# releBoard_v20.net
KiCad netlist of a schematic drawn in EAGLE
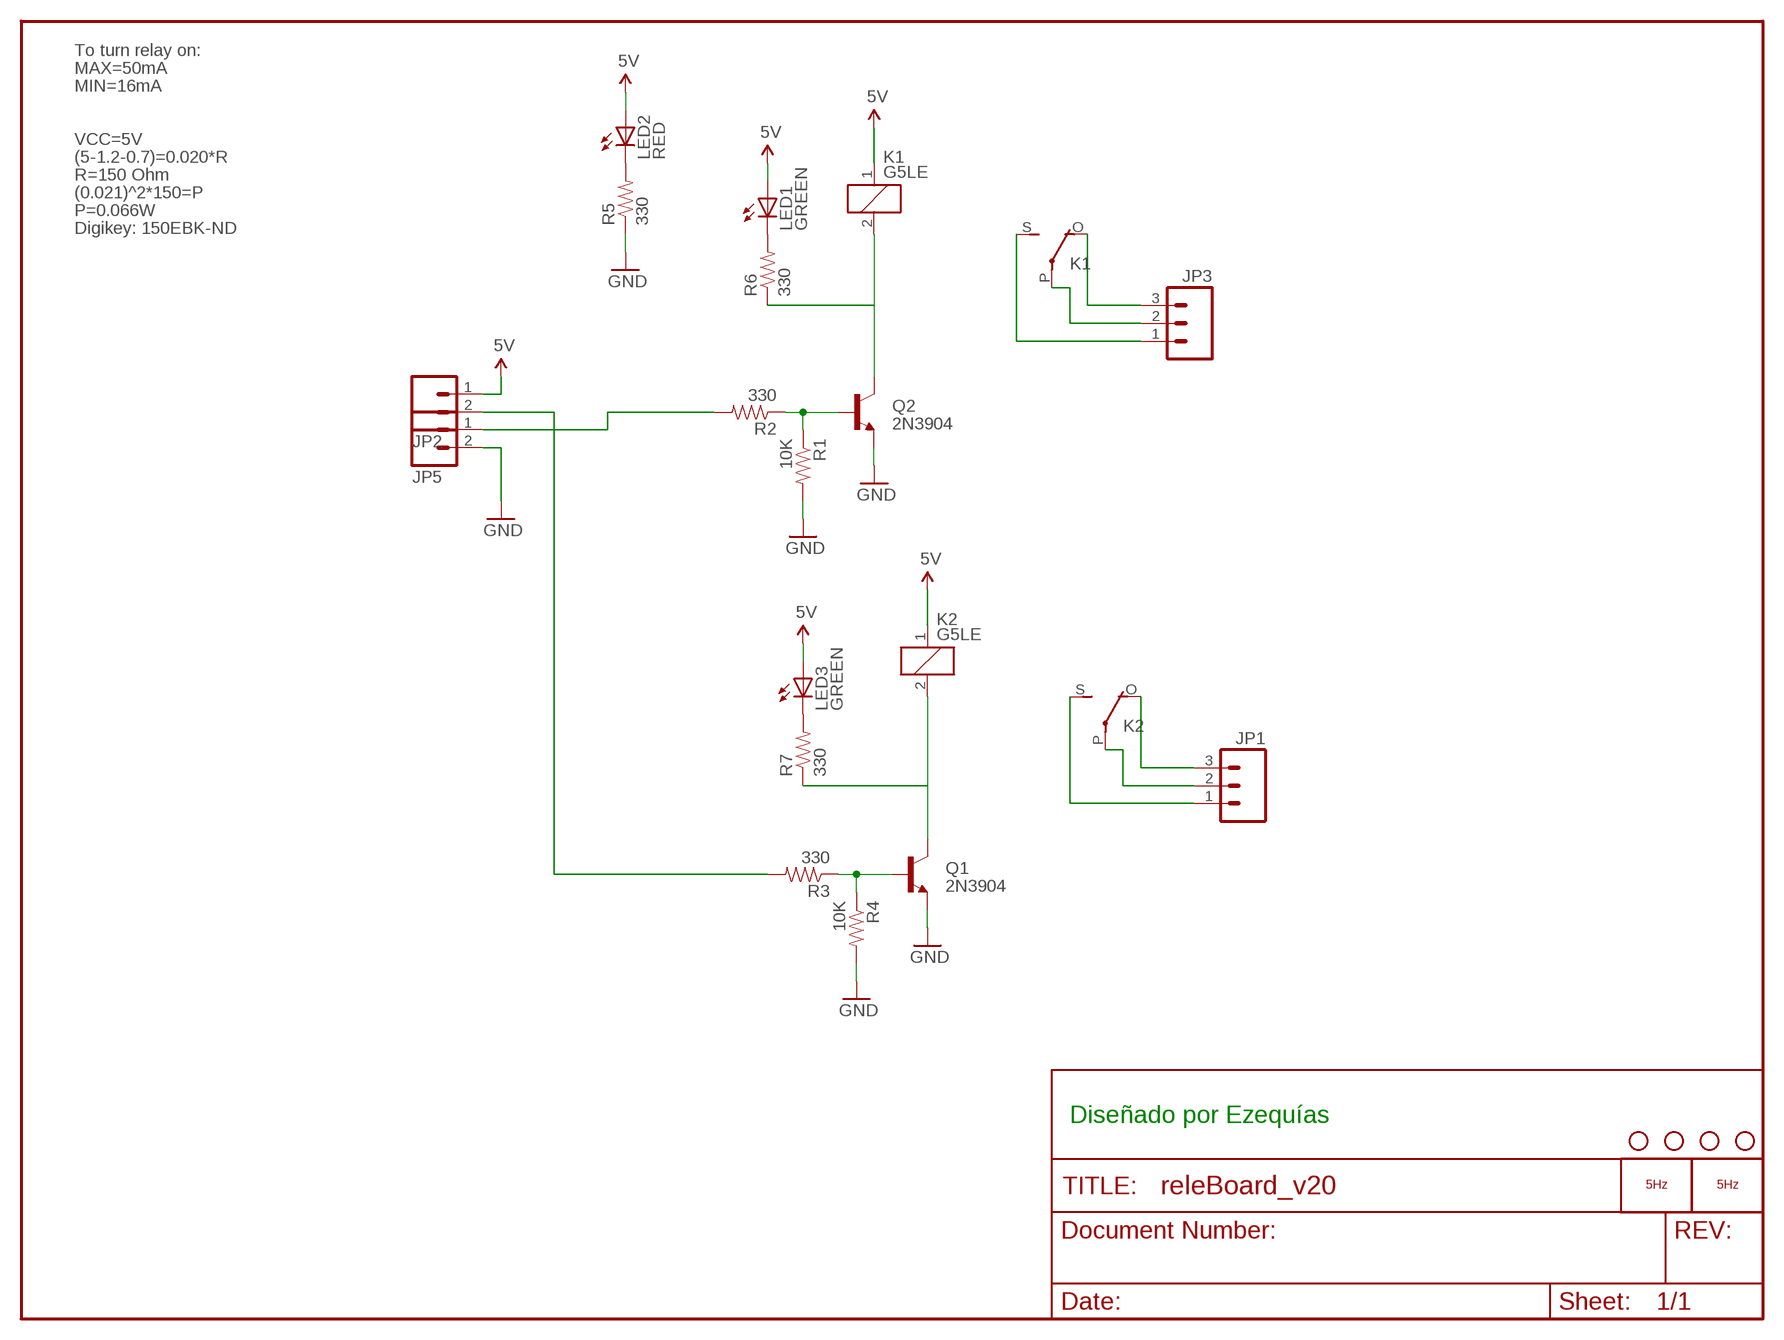
[diagram p0: schematic, sheet 1]

(export (version "E")
  (design (tool "Eeschema 10.0.6"))
  (components
    (comp (ref "JP1")
      (value "M03-SCREW-5MM")
      (footprint "eagle-import:SCREWTERMINAL-5MM-3")
      (libsource (lib "eagle-import") (part "M03-SCREW-5MM"))
    )
    (comp (ref "JP2")
      (value "M025MM")
      (footprint "eagle-import:SCREWTERMINAL-5MM-2")
      (libsource (lib "eagle-import") (part "M025MM"))
    )
    (comp (ref "JP3")
      (value "M03-SCREW-5MM")
      (footprint "eagle-import:SCREWTERMINAL-5MM-3")
      (libsource (lib "eagle-import") (part "M03-SCREW-5MM"))
    )
    (comp (ref "JP5")
      (value "M025MM")
      (footprint "eagle-import:SCREWTERMINAL-5MM-2")
      (libsource (lib "eagle-import") (part "M025MM"))
    )
    (comp (ref "K1")
      (value "G5LE")
      (footprint "eagle-import:G5LE")
      (libsource (lib "eagle-import") (part "G5LE"))
    )
    (comp (ref "K2")
      (value "G5LE")
      (footprint "eagle-import:G5LE")
      (libsource (lib "eagle-import") (part "G5LE"))
    )
    (comp (ref "LED1")
      (value "GREEN")
      (footprint "eagle-import:LED-0603")
      (libsource (lib "eagle-import") (part "LED0603"))
    )
    (comp (ref "LED2")
      (value "RED")
      (footprint "eagle-import:LED-0603")
      (libsource (lib "eagle-import") (part "LED0603"))
    )
    (comp (ref "LED3")
      (value "GREEN")
      (footprint "eagle-import:LED-0603")
      (libsource (lib "eagle-import") (part "LED0603"))
    )
    (comp (ref "LOGO1")
      (value "LOGO_5HZ_H_15MM")
      (footprint "eagle-import:5HZ_LOGO_H_15MM")
      (libsource (lib "eagle-import") (part "LOGO_5HZ_H_15MM"))
    )
    (comp (ref "LOGO2")
      (value "LOGO_5HZ_WEB_COOPER_10MM")
      (footprint "eagle-import:5HZ_WEB_COOPER_10MM")
      (libsource (lib "eagle-import") (part "LOGO_5HZ_WEB_COOPER_10MM"))
    )
    (comp (ref "Q1")
      (value "2N3904")
      (footprint "eagle-import:SOT23")
      (libsource (lib "eagle-import") (part "TRANSISTOR_NPNSOT23"))
    )
    (comp (ref "Q2")
      (value "2N3904")
      (footprint "eagle-import:SOT23")
      (libsource (lib "eagle-import") (part "TRANSISTOR_NPNSOT23"))
    )
    (comp (ref "R1")
      (value "10K")
      (footprint "eagle-import:0603-RES")
      (libsource (lib "eagle-import") (part "RESISTOR0603-RES"))
    )
    (comp (ref "R2")
      (value "330")
      (footprint "eagle-import:0603-RES")
      (libsource (lib "eagle-import") (part "RESISTOR0603-RES"))
    )
    (comp (ref "R3")
      (value "330")
      (footprint "eagle-import:0603-RES")
      (libsource (lib "eagle-import") (part "RESISTOR0603-RES"))
    )
    (comp (ref "R4")
      (value "10K")
      (footprint "eagle-import:0603-RES")
      (libsource (lib "eagle-import") (part "RESISTOR0603-RES"))
    )
    (comp (ref "R5")
      (value "330")
      (footprint "eagle-import:0603-RES")
      (libsource (lib "eagle-import") (part "RESISTOR0603-RES"))
    )
    (comp (ref "R6")
      (value "330")
      (footprint "eagle-import:0603-RES")
      (libsource (lib "eagle-import") (part "RESISTOR0603-RES"))
    )
    (comp (ref "R7")
      (value "330")
      (footprint "eagle-import:0603-RES")
      (libsource (lib "eagle-import") (part "RESISTOR0603-RES"))
    )
    (comp (ref "U$3")
      (value "STAND-OFF")
      (footprint "eagle-import:STAND-OFF")
      (libsource (lib "eagle-import") (part "STAND-OFF"))
    )
    (comp (ref "U$4")
      (value "STAND-OFF")
      (footprint "eagle-import:STAND-OFF")
      (libsource (lib "eagle-import") (part "STAND-OFF"))
    )
    (comp (ref "U$5")
      (value "STAND-OFF")
      (footprint "eagle-import:STAND-OFF")
      (libsource (lib "eagle-import") (part "STAND-OFF"))
    )
    (comp (ref "U$7")
      (value "STAND-OFF")
      (footprint "eagle-import:STAND-OFF")
      (libsource (lib "eagle-import") (part "STAND-OFF"))
    )
  )
  (nets
    (net (code "1") (name "5V") (class "Default")
      (node (ref "JP2") (pin "1") (pinfunction "1_1") (pintype "passive"))
      (node (ref "K1") (pin "1") (pinfunction "1_1") (pintype "passive"))
      (node (ref "K2") (pin "1") (pinfunction "1_1") (pintype "passive"))
      (node (ref "LED1") (pin "A") (pinfunction "A_A") (pintype "passive"))
      (node (ref "LED2") (pin "A") (pinfunction "A_A") (pintype "passive"))
      (node (ref "LED3") (pin "A") (pinfunction "A_A") (pintype "passive"))
    )
    (net (code "2") (name "GND") (class "Default")
      (node (ref "JP5") (pin "2") (pinfunction "2_2") (pintype "passive"))
      (node (ref "Q1") (pin "2") (pinfunction "E_2") (pintype "passive"))
      (node (ref "Q2") (pin "2") (pinfunction "E_2") (pintype "passive"))
      (node (ref "R1") (pin "2") (pinfunction "2_2") (pintype "passive"))
      (node (ref "R4") (pin "2") (pinfunction "2_2") (pintype "passive"))
      (node (ref "R5") (pin "1") (pinfunction "1_1") (pintype "passive"))
    )
    (net (code "3") (name "Net-(JP1-Pad1)") (class "Default")
      (node (ref "JP1") (pin "1") (pinfunction "1_1") (pintype "passive"))
      (node (ref "K2") (pin "S") (pinfunction "S_S") (pintype "passive"))
    )
    (net (code "4") (name "Net-(JP1-Pad2)") (class "Default")
      (node (ref "JP1") (pin "2") (pinfunction "2_2") (pintype "passive"))
      (node (ref "K2") (pin "P") (pinfunction "P_P") (pintype "passive"))
    )
    (net (code "5") (name "Net-(JP1-Pad3)") (class "Default")
      (node (ref "JP1") (pin "3") (pinfunction "3_3") (pintype "passive"))
      (node (ref "K2") (pin "O") (pinfunction "O_O") (pintype "passive"))
    )
    (net (code "6") (name "Net-(JP2-Pad2)") (class "Default")
      (node (ref "JP2") (pin "2") (pinfunction "2_2") (pintype "passive"))
      (node (ref "R3") (pin "2") (pinfunction "2_2") (pintype "passive"))
    )
    (net (code "7") (name "Net-(JP3-Pad1)") (class "Default")
      (node (ref "JP3") (pin "1") (pinfunction "1_1") (pintype "passive"))
      (node (ref "K1") (pin "S") (pinfunction "S_S") (pintype "passive"))
    )
    (net (code "8") (name "Net-(JP3-Pad2)") (class "Default")
      (node (ref "JP3") (pin "2") (pinfunction "2_2") (pintype "passive"))
      (node (ref "K1") (pin "P") (pinfunction "P_P") (pintype "passive"))
    )
    (net (code "9") (name "Net-(JP3-Pad3)") (class "Default")
      (node (ref "JP3") (pin "3") (pinfunction "3_3") (pintype "passive"))
      (node (ref "K1") (pin "O") (pinfunction "O_O") (pintype "passive"))
    )
    (net (code "10") (name "Net-(JP5-Pad1)") (class "Default")
      (node (ref "JP5") (pin "1") (pinfunction "1_1") (pintype "passive"))
      (node (ref "R2") (pin "2") (pinfunction "2_2") (pintype "passive"))
    )
    (net (code "11") (name "Net-(LED1-PadC)") (class "Default")
      (node (ref "LED1") (pin "C") (pinfunction "C_C") (pintype "passive"))
      (node (ref "R6") (pin "2") (pinfunction "2_2") (pintype "passive"))
    )
    (net (code "12") (name "Net-(LED2-PadC)") (class "Default")
      (node (ref "LED2") (pin "C") (pinfunction "C_C") (pintype "passive"))
      (node (ref "R5") (pin "2") (pinfunction "2_2") (pintype "passive"))
    )
    (net (code "13") (name "Net-(LED3-PadC)") (class "Default")
      (node (ref "LED3") (pin "C") (pinfunction "C_C") (pintype "passive"))
      (node (ref "R7") (pin "2") (pinfunction "2_2") (pintype "passive"))
    )
    (net (code "14") (name "Net-(Q1-B)") (class "Default")
      (node (ref "Q1") (pin "1") (pinfunction "B_1") (pintype "passive"))
      (node (ref "R3") (pin "1") (pinfunction "1_1") (pintype "passive"))
      (node (ref "R4") (pin "1") (pinfunction "1_1") (pintype "passive"))
    )
    (net (code "15") (name "Net-(Q1-C)") (class "Default")
      (node (ref "K2") (pin "2") (pinfunction "2_2") (pintype "passive"))
      (node (ref "Q1") (pin "3") (pinfunction "C_3") (pintype "passive"))
      (node (ref "R7") (pin "1") (pinfunction "1_1") (pintype "passive"))
    )
    (net (code "16") (name "Net-(Q2-B)") (class "Default")
      (node (ref "Q2") (pin "1") (pinfunction "B_1") (pintype "passive"))
      (node (ref "R1") (pin "1") (pinfunction "1_1") (pintype "passive"))
      (node (ref "R2") (pin "1") (pinfunction "1_1") (pintype "passive"))
    )
    (net (code "17") (name "Net-(Q2-C)") (class "Default")
      (node (ref "K1") (pin "2") (pinfunction "2_2") (pintype "passive"))
      (node (ref "Q2") (pin "3") (pinfunction "C_3") (pintype "passive"))
      (node (ref "R6") (pin "1") (pinfunction "1_1") (pintype "passive"))
    )
  )
)
